# half-stick.net
KiCad netlist of a schematic drawn in EAGLE
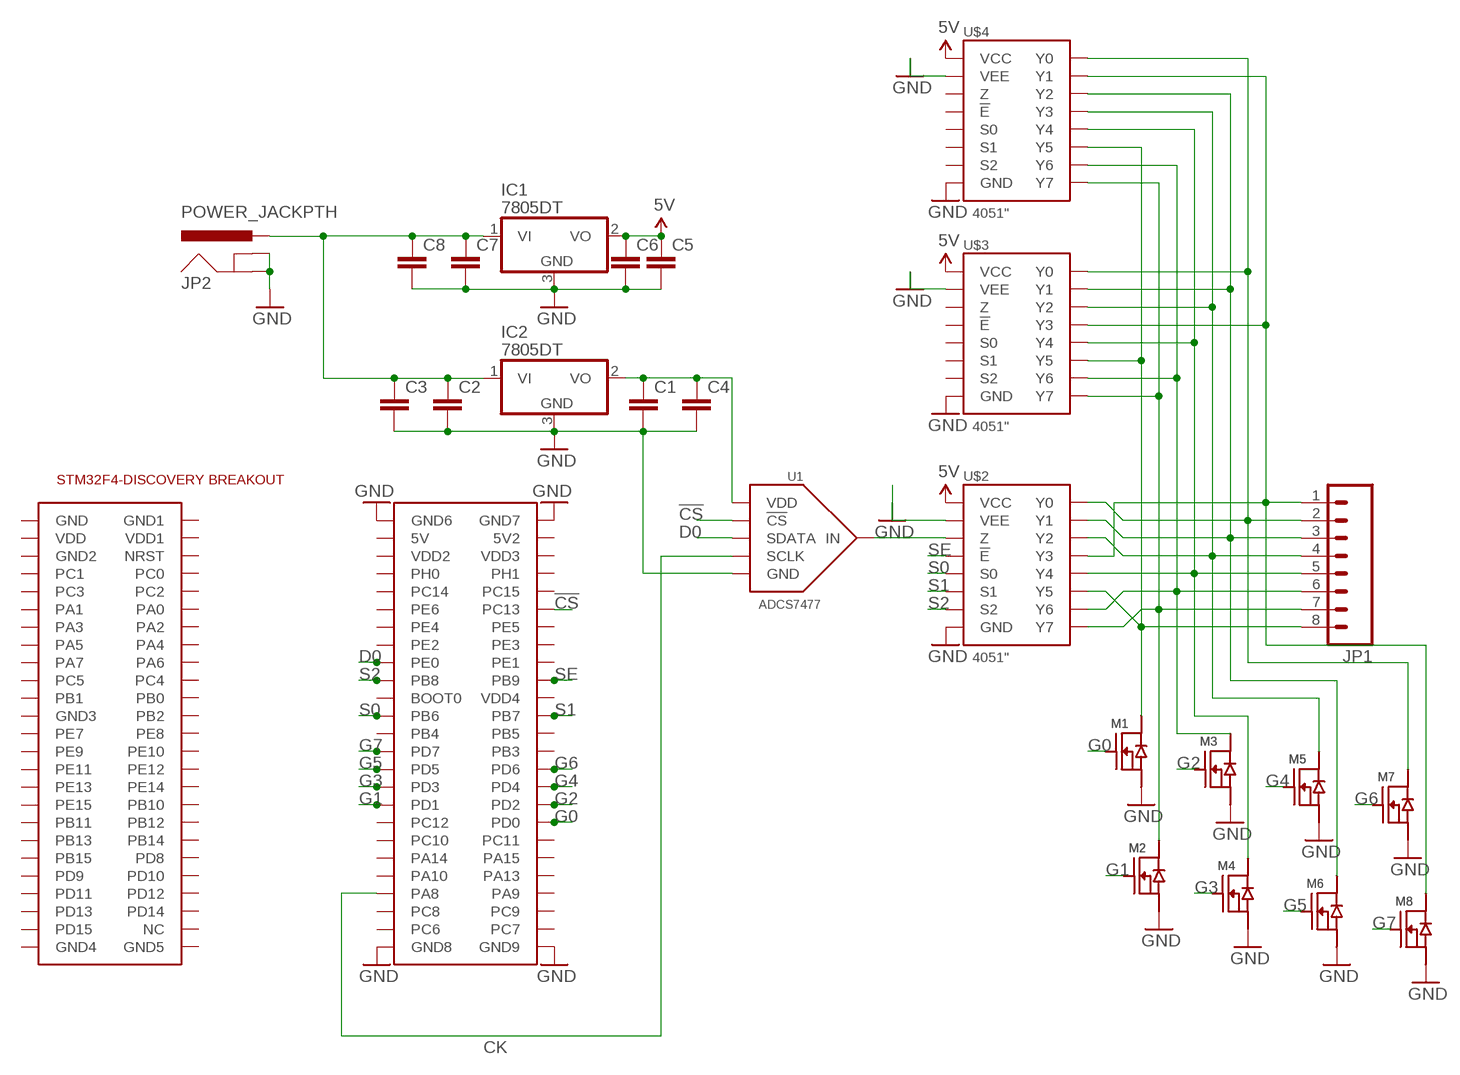
[diagram p0: schematic, sheet 1]

(export (version "E")
  (design (tool "Eeschema 10.0.6"))
  (components
    (comp (ref "C1")
      (value "C-EUC0805")
      (footprint "eagle-import:C0805")
      (libsource (lib "eagle-import") (part "C-EUC0805"))
    )
    (comp (ref "C2")
      (value "C-EUC0805")
      (footprint "eagle-import:C0805")
      (libsource (lib "eagle-import") (part "C-EUC0805"))
    )
    (comp (ref "C3")
      (value "C-EUC0805")
      (footprint "eagle-import:C0805")
      (libsource (lib "eagle-import") (part "C-EUC0805"))
    )
    (comp (ref "C4")
      (value "C-EUC0805")
      (footprint "eagle-import:C0805")
      (libsource (lib "eagle-import") (part "C-EUC0805"))
    )
    (comp (ref "C5")
      (value "C-EUC0805")
      (footprint "eagle-import:C0805")
      (libsource (lib "eagle-import") (part "C-EUC0805"))
    )
    (comp (ref "C6")
      (value "C-EUC0805")
      (footprint "eagle-import:C0805")
      (libsource (lib "eagle-import") (part "C-EUC0805"))
    )
    (comp (ref "C7")
      (value "C-EUC0805")
      (footprint "eagle-import:C0805")
      (libsource (lib "eagle-import") (part "C-EUC0805"))
    )
    (comp (ref "C8")
      (value "C-EUC0805")
      (footprint "eagle-import:C0805")
      (libsource (lib "eagle-import") (part "C-EUC0805"))
    )
    (comp (ref "IC1")
      (value "7805DT")
      (footprint "eagle-import:TO252")
      (libsource (lib "eagle-import") (part "78DT05"))
    )
    (comp (ref "IC2")
      (value "7805DT")
      (footprint "eagle-import:TO252")
      (libsource (lib "eagle-import") (part "78DT05"))
    )
    (comp (ref "JP1")
      (value "M08LONGPADS")
      (footprint "eagle-import:1X08_LONGPADS")
      (libsource (lib "eagle-import") (part "M08LONGPADS"))
    )
    (comp (ref "JP2")
      (value "POWER_JACKPTH")
      (footprint "eagle-import:POWER_JACK_PTH")
      (libsource (lib "eagle-import") (part "POWER_JACKPTH"))
    )
    (comp (ref "M1")
      (value "N-FET")
      (footprint "eagle-import:SOT23-3")
      (libsource (lib "eagle-import") (part "N-FET"))
    )
    (comp (ref "M2")
      (value "N-FET")
      (footprint "eagle-import:SOT23-3")
      (libsource (lib "eagle-import") (part "N-FET"))
    )
    (comp (ref "M3")
      (value "N-FET")
      (footprint "eagle-import:SOT23-3")
      (libsource (lib "eagle-import") (part "N-FET"))
    )
    (comp (ref "M4")
      (value "N-FET")
      (footprint "eagle-import:SOT23-3")
      (libsource (lib "eagle-import") (part "N-FET"))
    )
    (comp (ref "M5")
      (value "N-FET")
      (footprint "eagle-import:SOT23-3")
      (libsource (lib "eagle-import") (part "N-FET"))
    )
    (comp (ref "M6")
      (value "N-FET")
      (footprint "eagle-import:SOT23-3")
      (libsource (lib "eagle-import") (part "N-FET"))
    )
    (comp (ref "M7")
      (value "N-FET")
      (footprint "eagle-import:SOT23-3")
      (libsource (lib "eagle-import") (part "N-FET"))
    )
    (comp (ref "M8")
      (value "N-FET")
      (footprint "eagle-import:SOT23-3")
      (libsource (lib "eagle-import") (part "N-FET"))
    )
    (comp (ref "U$1")
      (value "STM32F4-DISCOVERY")
      (footprint "eagle-import:STM32F4-DISCOVERY")
      (libsource (lib "eagle-import") (part "STM32F4-DISCOVERY"))
    )
    (comp (ref "U$2")
      (value "4051\"")
      (footprint "eagle-import:TSSOP-16")
      (libsource (lib "eagle-import") (part "4051{dblquote}"))
    )
    (comp (ref "U$3")
      (value "4051\"")
      (footprint "eagle-import:TSSOP-16")
      (libsource (lib "eagle-import") (part "4051{dblquote}"))
    )
    (comp (ref "U$4")
      (value "4051\"")
      (footprint "eagle-import:TSSOP-16")
      (libsource (lib "eagle-import") (part "4051{dblquote}"))
    )
    (comp (ref "U1")
      (value "ADCS7477")
      (footprint "eagle-import:SOT-23-6")
      (libsource (lib "eagle-import") (part "ADCS7477"))
    )
  )
  (nets
    (net (code "1") (name "/CK") (class "Default")
      (node (ref "U$1") (pin "P$93") (pinfunction "PA8_P$93") (pintype "bidirectional"))
      (node (ref "U1") (pin "P$4") (pinfunction "SCLK_P$4") (pintype "bidirectional"))
    )
    (net (code "2") (name "/D0") (class "Default")
      (node (ref "U$1") (pin "P$67") (pinfunction "PE0_P$67") (pintype "bidirectional"))
      (node (ref "U1") (pin "P$5") (pinfunction "SDATA_P$5") (pintype "bidirectional"))
    )
    (net (code "3") (name "/G0") (class "Default")
      (node (ref "M1") (pin "1") (pinfunction "G_1") (pintype "bidirectional"))
      (node (ref "U$1") (pin "P$86") (pinfunction "PD0_P$86") (pintype "bidirectional"))
    )
    (net (code "4") (name "/G1") (class "Default")
      (node (ref "M2") (pin "1") (pinfunction "G_1") (pintype "bidirectional"))
      (node (ref "U$1") (pin "P$83") (pinfunction "PD1_P$83") (pintype "bidirectional"))
    )
    (net (code "5") (name "/G2") (class "Default")
      (node (ref "M3") (pin "1") (pinfunction "G_1") (pintype "bidirectional"))
      (node (ref "U$1") (pin "P$84") (pinfunction "PD2_P$84") (pintype "bidirectional"))
    )
    (net (code "6") (name "/G3") (class "Default")
      (node (ref "M4") (pin "1") (pinfunction "G_1") (pintype "bidirectional"))
      (node (ref "U$1") (pin "P$81") (pinfunction "PD3_P$81") (pintype "bidirectional"))
    )
    (net (code "7") (name "/G4") (class "Default")
      (node (ref "M5") (pin "1") (pinfunction "G_1") (pintype "bidirectional"))
      (node (ref "U$1") (pin "P$82") (pinfunction "PD4_P$82") (pintype "bidirectional"))
    )
    (net (code "8") (name "/G5") (class "Default")
      (node (ref "M6") (pin "1") (pinfunction "G_1") (pintype "bidirectional"))
      (node (ref "U$1") (pin "P$79") (pinfunction "PD5_P$79") (pintype "bidirectional"))
    )
    (net (code "9") (name "/G6") (class "Default")
      (node (ref "M7") (pin "1") (pinfunction "G_1") (pintype "bidirectional"))
      (node (ref "U$1") (pin "P$80") (pinfunction "PD6_P$80") (pintype "bidirectional"))
    )
    (net (code "10") (name "/G7") (class "Default")
      (node (ref "M8") (pin "1") (pinfunction "G_1") (pintype "bidirectional"))
      (node (ref "U$1") (pin "P$77") (pinfunction "PD7_P$77") (pintype "bidirectional"))
    )
    (net (code "11") (name "/S0") (class "Default")
      (node (ref "U$1") (pin "P$73") (pinfunction "PB6_P$73") (pintype "bidirectional"))
      (node (ref "U$2") (pin "P$11") (pinfunction "S0_P$11") (pintype "bidirectional"))
    )
    (net (code "12") (name "/S1") (class "Default")
      (node (ref "U$1") (pin "P$74") (pinfunction "PB7_P$74") (pintype "bidirectional"))
      (node (ref "U$2") (pin "P$10") (pinfunction "S1_P$10") (pintype "bidirectional"))
    )
    (net (code "13") (name "/S2") (class "Default")
      (node (ref "U$1") (pin "P$69") (pinfunction "PB8_P$69") (pintype "bidirectional"))
      (node (ref "U$2") (pin "P$9") (pinfunction "S2_P$9") (pintype "bidirectional"))
    )
    (net (code "14") (name "/SE") (class "Default")
      (node (ref "U$1") (pin "P$70") (pinfunction "PB9_P$70") (pintype "bidirectional"))
      (node (ref "U$2") (pin "P$6") (pinfunction "~{E}_P$6") (pintype "bidirectional"))
    )
    (net (code "15") (name "/~{CS}") (class "Default")
      (node (ref "U$1") (pin "P$62") (pinfunction "PC13_P$62") (pintype "bidirectional"))
      (node (ref "U1") (pin "P$6") (pinfunction "~{CS}_P$6") (pintype "bidirectional"))
    )
    (net (code "16") (name "5V") (class "Default")
      (node (ref "C5") (pin "1") (pinfunction "1_1") (pintype "passive"))
      (node (ref "C6") (pin "1") (pinfunction "1_1") (pintype "passive"))
      (node (ref "IC1") (pin "2") (pinfunction "VO_2") (pintype "passive"))
      (node (ref "U$2") (pin "P$16") (pinfunction "VCC_P$16") (pintype "bidirectional"))
      (node (ref "U$3") (pin "P$16") (pinfunction "VCC_P$16") (pintype "bidirectional"))
      (node (ref "U$4") (pin "P$16") (pinfunction "VCC_P$16") (pintype "bidirectional"))
    )
    (net (code "17") (name "GND") (class "Default")
      (node (ref "C1") (pin "2") (pinfunction "2_2") (pintype "passive"))
      (node (ref "C2") (pin "2") (pinfunction "2_2") (pintype "passive"))
      (node (ref "C3") (pin "2") (pinfunction "2_2") (pintype "passive"))
      (node (ref "C4") (pin "2") (pinfunction "2_2") (pintype "passive"))
      (node (ref "C5") (pin "2") (pinfunction "2_2") (pintype "passive"))
      (node (ref "C6") (pin "2") (pinfunction "2_2") (pintype "passive"))
      (node (ref "C7") (pin "2") (pinfunction "2_2") (pintype "passive"))
      (node (ref "C8") (pin "2") (pinfunction "2_2") (pintype "passive"))
      (node (ref "IC1") (pin "3") (pinfunction "GND_3") (pintype "passive"))
      (node (ref "IC2") (pin "3") (pinfunction "GND_3") (pintype "passive"))
      (node (ref "JP2") (pin "GND") (pinfunction "GND_GND") (pintype "bidirectional"))
      (node (ref "JP2") (pin "GNDBREAK") (pinfunction "GNDBREAK_GNDBREAK") (pintype "bidirectional"))
      (node (ref "M1") (pin "2") (pinfunction "S_2") (pintype "bidirectional"))
      (node (ref "M2") (pin "2") (pinfunction "S_2") (pintype "bidirectional"))
      (node (ref "M3") (pin "2") (pinfunction "S_2") (pintype "bidirectional"))
      (node (ref "M4") (pin "2") (pinfunction "S_2") (pintype "bidirectional"))
      (node (ref "M5") (pin "2") (pinfunction "S_2") (pintype "bidirectional"))
      (node (ref "M6") (pin "2") (pinfunction "S_2") (pintype "bidirectional"))
      (node (ref "M7") (pin "2") (pinfunction "S_2") (pintype "bidirectional"))
      (node (ref "M8") (pin "2") (pinfunction "S_2") (pintype "bidirectional"))
      (node (ref "U$1") (pin "P$100") (pinfunction "GND9_P$100") (pintype "bidirectional"))
      (node (ref "U$1") (pin "P$51") (pinfunction "GND6_P$51") (pintype "bidirectional"))
      (node (ref "U$1") (pin "P$52") (pinfunction "GND7_P$52") (pintype "bidirectional"))
      (node (ref "U$1") (pin "P$99") (pinfunction "GND8_P$99") (pintype "bidirectional"))
      (node (ref "U$2") (pin "P$7") (pinfunction "VEE_P$7") (pintype "bidirectional"))
      (node (ref "U$2") (pin "P$8") (pinfunction "GND_P$8") (pintype "bidirectional"))
      (node (ref "U$3") (pin "P$7") (pinfunction "VEE_P$7") (pintype "bidirectional"))
      (node (ref "U$3") (pin "P$8") (pinfunction "GND_P$8") (pintype "bidirectional"))
      (node (ref "U$4") (pin "P$7") (pinfunction "VEE_P$7") (pintype "bidirectional"))
      (node (ref "U$4") (pin "P$8") (pinfunction "GND_P$8") (pintype "bidirectional"))
      (node (ref "U1") (pin "P$2") (pinfunction "GND_P$2") (pintype "bidirectional"))
    )
    (net (code "18") (name "Net-(IC1-VI)") (class "Default")
      (node (ref "C2") (pin "1") (pinfunction "1_1") (pintype "passive"))
      (node (ref "C3") (pin "1") (pinfunction "1_1") (pintype "passive"))
      (node (ref "C7") (pin "1") (pinfunction "1_1") (pintype "passive"))
      (node (ref "C8") (pin "1") (pinfunction "1_1") (pintype "passive"))
      (node (ref "IC1") (pin "1") (pinfunction "VI_1") (pintype "input"))
      (node (ref "IC2") (pin "1") (pinfunction "VI_1") (pintype "input"))
      (node (ref "JP2") (pin "PWR") (pinfunction "PWR_PWR") (pintype "bidirectional"))
    )
    (net (code "19") (name "Net-(IC2-VO)") (class "Default")
      (node (ref "C1") (pin "1") (pinfunction "1_1") (pintype "passive"))
      (node (ref "C4") (pin "1") (pinfunction "1_1") (pintype "passive"))
      (node (ref "IC2") (pin "2") (pinfunction "VO_2") (pintype "passive"))
      (node (ref "U1") (pin "P$1") (pinfunction "VDD_P$1") (pintype "bidirectional"))
    )
    (net (code "20") (name "Net-(M1-D)") (class "Default")
      (node (ref "JP1") (pin "8") (pinfunction "8_8") (pintype "passive"))
      (node (ref "M1") (pin "3") (pinfunction "D_3") (pintype "bidirectional"))
      (node (ref "U$2") (pin "P$5") (pinfunction "Y5_P$5") (pintype "bidirectional"))
      (node (ref "U$3") (pin "P$5") (pinfunction "Y5_P$5") (pintype "bidirectional"))
      (node (ref "U$4") (pin "P$5") (pinfunction "Y5_P$5") (pintype "bidirectional"))
    )
    (net (code "21") (name "Net-(M2-D)") (class "Default")
      (node (ref "JP1") (pin "7") (pinfunction "7_7") (pintype "passive"))
      (node (ref "M2") (pin "3") (pinfunction "D_3") (pintype "bidirectional"))
      (node (ref "U$2") (pin "P$4") (pinfunction "Y7_P$4") (pintype "bidirectional"))
      (node (ref "U$3") (pin "P$4") (pinfunction "Y7_P$4") (pintype "bidirectional"))
      (node (ref "U$4") (pin "P$4") (pinfunction "Y7_P$4") (pintype "bidirectional"))
    )
    (net (code "22") (name "Net-(M3-D)") (class "Default")
      (node (ref "JP1") (pin "6") (pinfunction "6_6") (pintype "passive"))
      (node (ref "M3") (pin "3") (pinfunction "D_3") (pintype "bidirectional"))
      (node (ref "U$2") (pin "P$2") (pinfunction "Y6_P$2") (pintype "bidirectional"))
      (node (ref "U$3") (pin "P$2") (pinfunction "Y6_P$2") (pintype "bidirectional"))
      (node (ref "U$4") (pin "P$2") (pinfunction "Y6_P$2") (pintype "bidirectional"))
    )
    (net (code "23") (name "Net-(M4-D)") (class "Default")
      (node (ref "JP1") (pin "5") (pinfunction "5_5") (pintype "passive"))
      (node (ref "M4") (pin "3") (pinfunction "D_3") (pintype "bidirectional"))
      (node (ref "U$2") (pin "P$1") (pinfunction "Y4_P$1") (pintype "bidirectional"))
      (node (ref "U$3") (pin "P$1") (pinfunction "Y4_P$1") (pintype "bidirectional"))
      (node (ref "U$4") (pin "P$1") (pinfunction "Y4_P$1") (pintype "bidirectional"))
    )
    (net (code "24") (name "Net-(M5-D)") (class "Default")
      (node (ref "JP1") (pin "4") (pinfunction "4_4") (pintype "passive"))
      (node (ref "M5") (pin "3") (pinfunction "D_3") (pintype "bidirectional"))
      (node (ref "U$2") (pin "P$15") (pinfunction "Y2_P$15") (pintype "bidirectional"))
      (node (ref "U$3") (pin "P$15") (pinfunction "Y2_P$15") (pintype "bidirectional"))
      (node (ref "U$4") (pin "P$12") (pinfunction "Y3_P$12") (pintype "bidirectional"))
    )
    (net (code "25") (name "Net-(M6-D)") (class "Default")
      (node (ref "JP1") (pin "3") (pinfunction "3_3") (pintype "passive"))
      (node (ref "M6") (pin "3") (pinfunction "D_3") (pintype "bidirectional"))
      (node (ref "U$2") (pin "P$14") (pinfunction "Y1_P$14") (pintype "bidirectional"))
      (node (ref "U$3") (pin "P$14") (pinfunction "Y1_P$14") (pintype "bidirectional"))
      (node (ref "U$4") (pin "P$15") (pinfunction "Y2_P$15") (pintype "bidirectional"))
    )
    (net (code "26") (name "Net-(M7-D)") (class "Default")
      (node (ref "JP1") (pin "2") (pinfunction "2_2") (pintype "passive"))
      (node (ref "M7") (pin "3") (pinfunction "D_3") (pintype "bidirectional"))
      (node (ref "U$2") (pin "P$13") (pinfunction "Y0_P$13") (pintype "bidirectional"))
      (node (ref "U$3") (pin "P$13") (pinfunction "Y0_P$13") (pintype "bidirectional"))
      (node (ref "U$4") (pin "P$13") (pinfunction "Y0_P$13") (pintype "bidirectional"))
    )
    (net (code "27") (name "Net-(M8-D)") (class "Default")
      (node (ref "JP1") (pin "1") (pinfunction "1_1") (pintype "passive"))
      (node (ref "M8") (pin "3") (pinfunction "D_3") (pintype "bidirectional"))
      (node (ref "U$2") (pin "P$12") (pinfunction "Y3_P$12") (pintype "bidirectional"))
      (node (ref "U$3") (pin "P$12") (pinfunction "Y3_P$12") (pintype "bidirectional"))
      (node (ref "U$4") (pin "P$14") (pinfunction "Y1_P$14") (pintype "bidirectional"))
    )
    (net (code "28") (name "Net-(U$2-Z)") (class "Default")
      (node (ref "U$2") (pin "P$3") (pinfunction "Z_P$3") (pintype "bidirectional"))
      (node (ref "U1") (pin "P$3") (pinfunction "IN_P$3") (pintype "bidirectional"))
    )
    (net (code "29") (name "unconnected-(U$1-5V-PadP$53)") (class "Default")
      (node (ref "U$1") (pin "P$53") (pinfunction "5V_P$53") (pintype "bidirectional"))
    )
    (net (code "30") (name "unconnected-(U$1-5V2-PadP$54)") (class "Default")
      (node (ref "U$1") (pin "P$54") (pinfunction "5V2_P$54") (pintype "bidirectional"))
    )
    (net (code "31") (name "unconnected-(U$1-BOOT0-PadP$71)") (class "Default")
      (node (ref "U$1") (pin "P$71") (pinfunction "BOOT0_P$71") (pintype "bidirectional"))
    )
    (net (code "32") (name "unconnected-(U$1-GND-PadP$1)") (class "Default")
      (node (ref "U$1") (pin "P$1") (pinfunction "GND_P$1") (pintype "bidirectional"))
    )
    (net (code "33") (name "unconnected-(U$1-GND1-PadP$2)") (class "Default")
      (node (ref "U$1") (pin "P$2") (pinfunction "GND1_P$2") (pintype "bidirectional"))
    )
    (net (code "34") (name "unconnected-(U$1-GND2-PadP$5)") (class "Default")
      (node (ref "U$1") (pin "P$5") (pinfunction "GND2_P$5") (pintype "bidirectional"))
    )
    (net (code "35") (name "unconnected-(U$1-GND3-PadP$23)") (class "Default")
      (node (ref "U$1") (pin "P$23") (pinfunction "GND3_P$23") (pintype "bidirectional"))
    )
    (net (code "36") (name "unconnected-(U$1-GND4-PadP$49)") (class "Default")
      (node (ref "U$1") (pin "P$49") (pinfunction "GND4_P$49") (pintype "bidirectional"))
    )
    (net (code "37") (name "unconnected-(U$1-GND5-PadP$50)") (class "Default")
      (node (ref "U$1") (pin "P$50") (pinfunction "GND5_P$50") (pintype "bidirectional"))
    )
    (net (code "38") (name "unconnected-(U$1-NC-PadP$48)") (class "Default")
      (node (ref "U$1") (pin "P$48") (pinfunction "NC_P$48") (pintype "bidirectional"))
    )
    (net (code "39") (name "unconnected-(U$1-NRST-PadP$6)") (class "Default")
      (node (ref "U$1") (pin "P$6") (pinfunction "NRST_P$6") (pintype "bidirectional"))
    )
    (net (code "40") (name "unconnected-(U$1-PA0-PadP$12)") (class "Default")
      (node (ref "U$1") (pin "P$12") (pinfunction "PA0_P$12") (pintype "bidirectional"))
    )
    (net (code "41") (name "unconnected-(U$1-PA1-PadP$11)") (class "Default")
      (node (ref "U$1") (pin "P$11") (pinfunction "PA1_P$11") (pintype "bidirectional"))
    )
    (net (code "42") (name "unconnected-(U$1-PA2-PadP$14)") (class "Default")
      (node (ref "U$1") (pin "P$14") (pinfunction "PA2_P$14") (pintype "bidirectional"))
    )
    (net (code "43") (name "unconnected-(U$1-PA3-PadP$13)") (class "Default")
      (node (ref "U$1") (pin "P$13") (pinfunction "PA3_P$13") (pintype "bidirectional"))
    )
    (net (code "44") (name "unconnected-(U$1-PA4-PadP$16)") (class "Default")
      (node (ref "U$1") (pin "P$16") (pinfunction "PA4_P$16") (pintype "bidirectional"))
    )
    (net (code "45") (name "unconnected-(U$1-PA5-PadP$15)") (class "Default")
      (node (ref "U$1") (pin "P$15") (pinfunction "PA5_P$15") (pintype "bidirectional"))
    )
    (net (code "46") (name "unconnected-(U$1-PA6-PadP$18)") (class "Default")
      (node (ref "U$1") (pin "P$18") (pinfunction "PA6_P$18") (pintype "bidirectional"))
    )
    (net (code "47") (name "unconnected-(U$1-PA7-PadP$17)") (class "Default")
      (node (ref "U$1") (pin "P$17") (pinfunction "PA7_P$17") (pintype "bidirectional"))
    )
    (net (code "48") (name "unconnected-(U$1-PA9-PadP$94)") (class "Default")
      (node (ref "U$1") (pin "P$94") (pinfunction "PA9_P$94") (pintype "bidirectional"))
    )
    (net (code "49") (name "unconnected-(U$1-PA10-PadP$91)") (class "Default")
      (node (ref "U$1") (pin "P$91") (pinfunction "PA10_P$91") (pintype "bidirectional"))
    )
    (net (code "50") (name "unconnected-(U$1-PA13-PadP$92)") (class "Default")
      (node (ref "U$1") (pin "P$92") (pinfunction "PA13_P$92") (pintype "bidirectional"))
    )
    (net (code "51") (name "unconnected-(U$1-PA14-PadP$89)") (class "Default")
      (node (ref "U$1") (pin "P$89") (pinfunction "PA14_P$89") (pintype "bidirectional"))
    )
    (net (code "52") (name "unconnected-(U$1-PA15-PadP$90)") (class "Default")
      (node (ref "U$1") (pin "P$90") (pinfunction "PA15_P$90") (pintype "bidirectional"))
    )
    (net (code "53") (name "unconnected-(U$1-PB0-PadP$22)") (class "Default")
      (node (ref "U$1") (pin "P$22") (pinfunction "PB0_P$22") (pintype "bidirectional"))
    )
    (net (code "54") (name "unconnected-(U$1-PB1-PadP$21)") (class "Default")
      (node (ref "U$1") (pin "P$21") (pinfunction "PB1_P$21") (pintype "bidirectional"))
    )
    (net (code "55") (name "unconnected-(U$1-PB2-PadP$24)") (class "Default")
      (node (ref "U$1") (pin "P$24") (pinfunction "PB2_P$24") (pintype "bidirectional"))
    )
    (net (code "56") (name "unconnected-(U$1-PB3-PadP$78)") (class "Default")
      (node (ref "U$1") (pin "P$78") (pinfunction "PB3_P$78") (pintype "bidirectional"))
    )
    (net (code "57") (name "unconnected-(U$1-PB4-PadP$75)") (class "Default")
      (node (ref "U$1") (pin "P$75") (pinfunction "PB4_P$75") (pintype "bidirectional"))
    )
    (net (code "58") (name "unconnected-(U$1-PB5-PadP$76)") (class "Default")
      (node (ref "U$1") (pin "P$76") (pinfunction "PB5_P$76") (pintype "bidirectional"))
    )
    (net (code "59") (name "unconnected-(U$1-PB10-PadP$34)") (class "Default")
      (node (ref "U$1") (pin "P$34") (pinfunction "PB10_P$34") (pintype "bidirectional"))
    )
    (net (code "60") (name "unconnected-(U$1-PB11-PadP$35)") (class "Default")
      (node (ref "U$1") (pin "P$35") (pinfunction "PB11_P$35") (pintype "bidirectional"))
    )
    (net (code "61") (name "unconnected-(U$1-PB12-PadP$36)") (class "Default")
      (node (ref "U$1") (pin "P$36") (pinfunction "PB12_P$36") (pintype "bidirectional"))
    )
    (net (code "62") (name "unconnected-(U$1-PB13-PadP$37)") (class "Default")
      (node (ref "U$1") (pin "P$37") (pinfunction "PB13_P$37") (pintype "bidirectional"))
    )
    (net (code "63") (name "unconnected-(U$1-PB14-PadP$38)") (class "Default")
      (node (ref "U$1") (pin "P$38") (pinfunction "PB14_P$38") (pintype "bidirectional"))
    )
    (net (code "64") (name "unconnected-(U$1-PB15-PadP$39)") (class "Default")
      (node (ref "U$1") (pin "P$39") (pinfunction "PB15_P$39") (pintype "bidirectional"))
    )
    (net (code "65") (name "unconnected-(U$1-PC0-PadP$8)") (class "Default")
      (node (ref "U$1") (pin "P$8") (pinfunction "PC0_P$8") (pintype "bidirectional"))
    )
    (net (code "66") (name "unconnected-(U$1-PC1-PadP$7)") (class "Default")
      (node (ref "U$1") (pin "P$7") (pinfunction "PC1_P$7") (pintype "bidirectional"))
    )
    (net (code "67") (name "unconnected-(U$1-PC2-PadP$10)") (class "Default")
      (node (ref "U$1") (pin "P$10") (pinfunction "PC2_P$10") (pintype "bidirectional"))
    )
    (net (code "68") (name "unconnected-(U$1-PC3-PadP$9)") (class "Default")
      (node (ref "U$1") (pin "P$9") (pinfunction "PC3_P$9") (pintype "bidirectional"))
    )
    (net (code "69") (name "unconnected-(U$1-PC4-PadP$20)") (class "Default")
      (node (ref "U$1") (pin "P$20") (pinfunction "PC4_P$20") (pintype "bidirectional"))
    )
    (net (code "70") (name "unconnected-(U$1-PC5-PadP$19)") (class "Default")
      (node (ref "U$1") (pin "P$19") (pinfunction "PC5_P$19") (pintype "bidirectional"))
    )
    (net (code "71") (name "unconnected-(U$1-PC6-PadP$97)") (class "Default")
      (node (ref "U$1") (pin "P$97") (pinfunction "PC6_P$97") (pintype "bidirectional"))
    )
    (net (code "72") (name "unconnected-(U$1-PC7-PadP$98)") (class "Default")
      (node (ref "U$1") (pin "P$98") (pinfunction "PC7_P$98") (pintype "bidirectional"))
    )
    (net (code "73") (name "unconnected-(U$1-PC8-PadP$95)") (class "Default")
      (node (ref "U$1") (pin "P$95") (pinfunction "PC8_P$95") (pintype "bidirectional"))
    )
    (net (code "74") (name "unconnected-(U$1-PC9-PadP$96)") (class "Default")
      (node (ref "U$1") (pin "P$96") (pinfunction "PC9_P$96") (pintype "bidirectional"))
    )
    (net (code "75") (name "unconnected-(U$1-PC10-PadP$87)") (class "Default")
      (node (ref "U$1") (pin "P$87") (pinfunction "PC10_P$87") (pintype "bidirectional"))
    )
    (net (code "76") (name "unconnected-(U$1-PC11-PadP$88)") (class "Default")
      (node (ref "U$1") (pin "P$88") (pinfunction "PC11_P$88") (pintype "bidirectional"))
    )
    (net (code "77") (name "unconnected-(U$1-PC12-PadP$85)") (class "Default")
      (node (ref "U$1") (pin "P$85") (pinfunction "PC12_P$85") (pintype "bidirectional"))
    )
    (net (code "78") (name "unconnected-(U$1-PC14-PadP$59)") (class "Default")
      (node (ref "U$1") (pin "P$59") (pinfunction "PC14_P$59") (pintype "bidirectional"))
    )
    (net (code "79") (name "unconnected-(U$1-PC15-PadP$60)") (class "Default")
      (node (ref "U$1") (pin "P$60") (pinfunction "PC15_P$60") (pintype "bidirectional"))
    )
    (net (code "80") (name "unconnected-(U$1-PD8-PadP$40)") (class "Default")
      (node (ref "U$1") (pin "P$40") (pinfunction "PD8_P$40") (pintype "bidirectional"))
    )
    (net (code "81") (name "unconnected-(U$1-PD9-PadP$41)") (class "Default")
      (node (ref "U$1") (pin "P$41") (pinfunction "PD9_P$41") (pintype "bidirectional"))
    )
    (net (code "82") (name "unconnected-(U$1-PD10-PadP$42)") (class "Default")
      (node (ref "U$1") (pin "P$42") (pinfunction "PD10_P$42") (pintype "bidirectional"))
    )
    (net (code "83") (name "unconnected-(U$1-PD11-PadP$43)") (class "Default")
      (node (ref "U$1") (pin "P$43") (pinfunction "PD11_P$43") (pintype "bidirectional"))
    )
    (net (code "84") (name "unconnected-(U$1-PD12-PadP$44)") (class "Default")
      (node (ref "U$1") (pin "P$44") (pinfunction "PD12_P$44") (pintype "bidirectional"))
    )
    (net (code "85") (name "unconnected-(U$1-PD13-PadP$45)") (class "Default")
      (node (ref "U$1") (pin "P$45") (pinfunction "PD13_P$45") (pintype "bidirectional"))
    )
    (net (code "86") (name "unconnected-(U$1-PD14-PadP$46)") (class "Default")
      (node (ref "U$1") (pin "P$46") (pinfunction "PD14_P$46") (pintype "bidirectional"))
    )
    (net (code "87") (name "unconnected-(U$1-PD15-PadP$47)") (class "Default")
      (node (ref "U$1") (pin "P$47") (pinfunction "PD15_P$47") (pintype "bidirectional"))
    )
    (net (code "88") (name "unconnected-(U$1-PE1-PadP$68)") (class "Default")
      (node (ref "U$1") (pin "P$68") (pinfunction "PE1_P$68") (pintype "bidirectional"))
    )
    (net (code "89") (name "unconnected-(U$1-PE2-PadP$65)") (class "Default")
      (node (ref "U$1") (pin "P$65") (pinfunction "PE2_P$65") (pintype "bidirectional"))
    )
    (net (code "90") (name "unconnected-(U$1-PE3-PadP$66)") (class "Default")
      (node (ref "U$1") (pin "P$66") (pinfunction "PE3_P$66") (pintype "bidirectional"))
    )
    (net (code "91") (name "unconnected-(U$1-PE4-PadP$63)") (class "Default")
      (node (ref "U$1") (pin "P$63") (pinfunction "PE4_P$63") (pintype "bidirectional"))
    )
    (net (code "92") (name "unconnected-(U$1-PE5-PadP$64)") (class "Default")
      (node (ref "U$1") (pin "P$64") (pinfunction "PE5_P$64") (pintype "bidirectional"))
    )
    (net (code "93") (name "unconnected-(U$1-PE6-PadP$61)") (class "Default")
      (node (ref "U$1") (pin "P$61") (pinfunction "PE6_P$61") (pintype "bidirectional"))
    )
    (net (code "94") (name "unconnected-(U$1-PE7-PadP$25)") (class "Default")
      (node (ref "U$1") (pin "P$25") (pinfunction "PE7_P$25") (pintype "bidirectional"))
    )
    (net (code "95") (name "unconnected-(U$1-PE8-PadP$26)") (class "Default")
      (node (ref "U$1") (pin "P$26") (pinfunction "PE8_P$26") (pintype "bidirectional"))
    )
    (net (code "96") (name "unconnected-(U$1-PE9-PadP$27)") (class "Default")
      (node (ref "U$1") (pin "P$27") (pinfunction "PE9_P$27") (pintype "bidirectional"))
    )
    (net (code "97") (name "unconnected-(U$1-PE10-PadP$28)") (class "Default")
      (node (ref "U$1") (pin "P$28") (pinfunction "PE10_P$28") (pintype "bidirectional"))
    )
    (net (code "98") (name "unconnected-(U$1-PE11-PadP$29)") (class "Default")
      (node (ref "U$1") (pin "P$29") (pinfunction "PE11_P$29") (pintype "bidirectional"))
    )
    (net (code "99") (name "unconnected-(U$1-PE12-PadP$30)") (class "Default")
      (node (ref "U$1") (pin "P$30") (pinfunction "PE12_P$30") (pintype "bidirectional"))
    )
    (net (code "100") (name "unconnected-(U$1-PE13-PadP$31)") (class "Default")
      (node (ref "U$1") (pin "P$31") (pinfunction "PE13_P$31") (pintype "bidirectional"))
    )
    (net (code "101") (name "unconnected-(U$1-PE14-PadP$32)") (class "Default")
      (node (ref "U$1") (pin "P$32") (pinfunction "PE14_P$32") (pintype "bidirectional"))
    )
    (net (code "102") (name "unconnected-(U$1-PE15-PadP$33)") (class "Default")
      (node (ref "U$1") (pin "P$33") (pinfunction "PE15_P$33") (pintype "bidirectional"))
    )
    (net (code "103") (name "unconnected-(U$1-PH0-PadP$57)") (class "Default")
      (node (ref "U$1") (pin "P$57") (pinfunction "PH0_P$57") (pintype "bidirectional"))
    )
    (net (code "104") (name "unconnected-(U$1-PH1-PadP$58)") (class "Default")
      (node (ref "U$1") (pin "P$58") (pinfunction "PH1_P$58") (pintype "bidirectional"))
    )
    (net (code "105") (name "unconnected-(U$1-VDD-PadP$3)") (class "Default")
      (node (ref "U$1") (pin "P$3") (pinfunction "VDD_P$3") (pintype "bidirectional"))
    )
    (net (code "106") (name "unconnected-(U$1-VDD1-PadP$4)") (class "Default")
      (node (ref "U$1") (pin "P$4") (pinfunction "VDD1_P$4") (pintype "bidirectional"))
    )
    (net (code "107") (name "unconnected-(U$1-VDD2-PadP$55)") (class "Default")
      (node (ref "U$1") (pin "P$55") (pinfunction "VDD2_P$55") (pintype "bidirectional"))
    )
    (net (code "108") (name "unconnected-(U$1-VDD3-PadP$56)") (class "Default")
      (node (ref "U$1") (pin "P$56") (pinfunction "VDD3_P$56") (pintype "bidirectional"))
    )
    (net (code "109") (name "unconnected-(U$1-VDD4-PadP$72)") (class "Default")
      (node (ref "U$1") (pin "P$72") (pinfunction "VDD4_P$72") (pintype "bidirectional"))
    )
    (net (code "110") (name "unconnected-(U$3-S0-PadP$11)") (class "Default")
      (node (ref "U$3") (pin "P$11") (pinfunction "S0_P$11") (pintype "bidirectional"))
    )
    (net (code "111") (name "unconnected-(U$3-S1-PadP$10)") (class "Default")
      (node (ref "U$3") (pin "P$10") (pinfunction "S1_P$10") (pintype "bidirectional"))
    )
    (net (code "112") (name "unconnected-(U$3-S2-PadP$9)") (class "Default")
      (node (ref "U$3") (pin "P$9") (pinfunction "S2_P$9") (pintype "bidirectional"))
    )
    (net (code "113") (name "unconnected-(U$3-Z-PadP$3)") (class "Default")
      (node (ref "U$3") (pin "P$3") (pinfunction "Z_P$3") (pintype "bidirectional"))
    )
    (net (code "114") (name "unconnected-(U$3-~{E}-PadP$6)") (class "Default")
      (node (ref "U$3") (pin "P$6") (pinfunction "~{E}_P$6") (pintype "bidirectional"))
    )
    (net (code "115") (name "unconnected-(U$4-S0-PadP$11)") (class "Default")
      (node (ref "U$4") (pin "P$11") (pinfunction "S0_P$11") (pintype "bidirectional"))
    )
    (net (code "116") (name "unconnected-(U$4-S1-PadP$10)") (class "Default")
      (node (ref "U$4") (pin "P$10") (pinfunction "S1_P$10") (pintype "bidirectional"))
    )
    (net (code "117") (name "unconnected-(U$4-S2-PadP$9)") (class "Default")
      (node (ref "U$4") (pin "P$9") (pinfunction "S2_P$9") (pintype "bidirectional"))
    )
    (net (code "118") (name "unconnected-(U$4-Z-PadP$3)") (class "Default")
      (node (ref "U$4") (pin "P$3") (pinfunction "Z_P$3") (pintype "bidirectional"))
    )
    (net (code "119") (name "unconnected-(U$4-~{E}-PadP$6)") (class "Default")
      (node (ref "U$4") (pin "P$6") (pinfunction "~{E}_P$6") (pintype "bidirectional"))
    )
  )
)
